# Power_Supply.net
KiCad netlist of a schematic drawn in Altium Designer
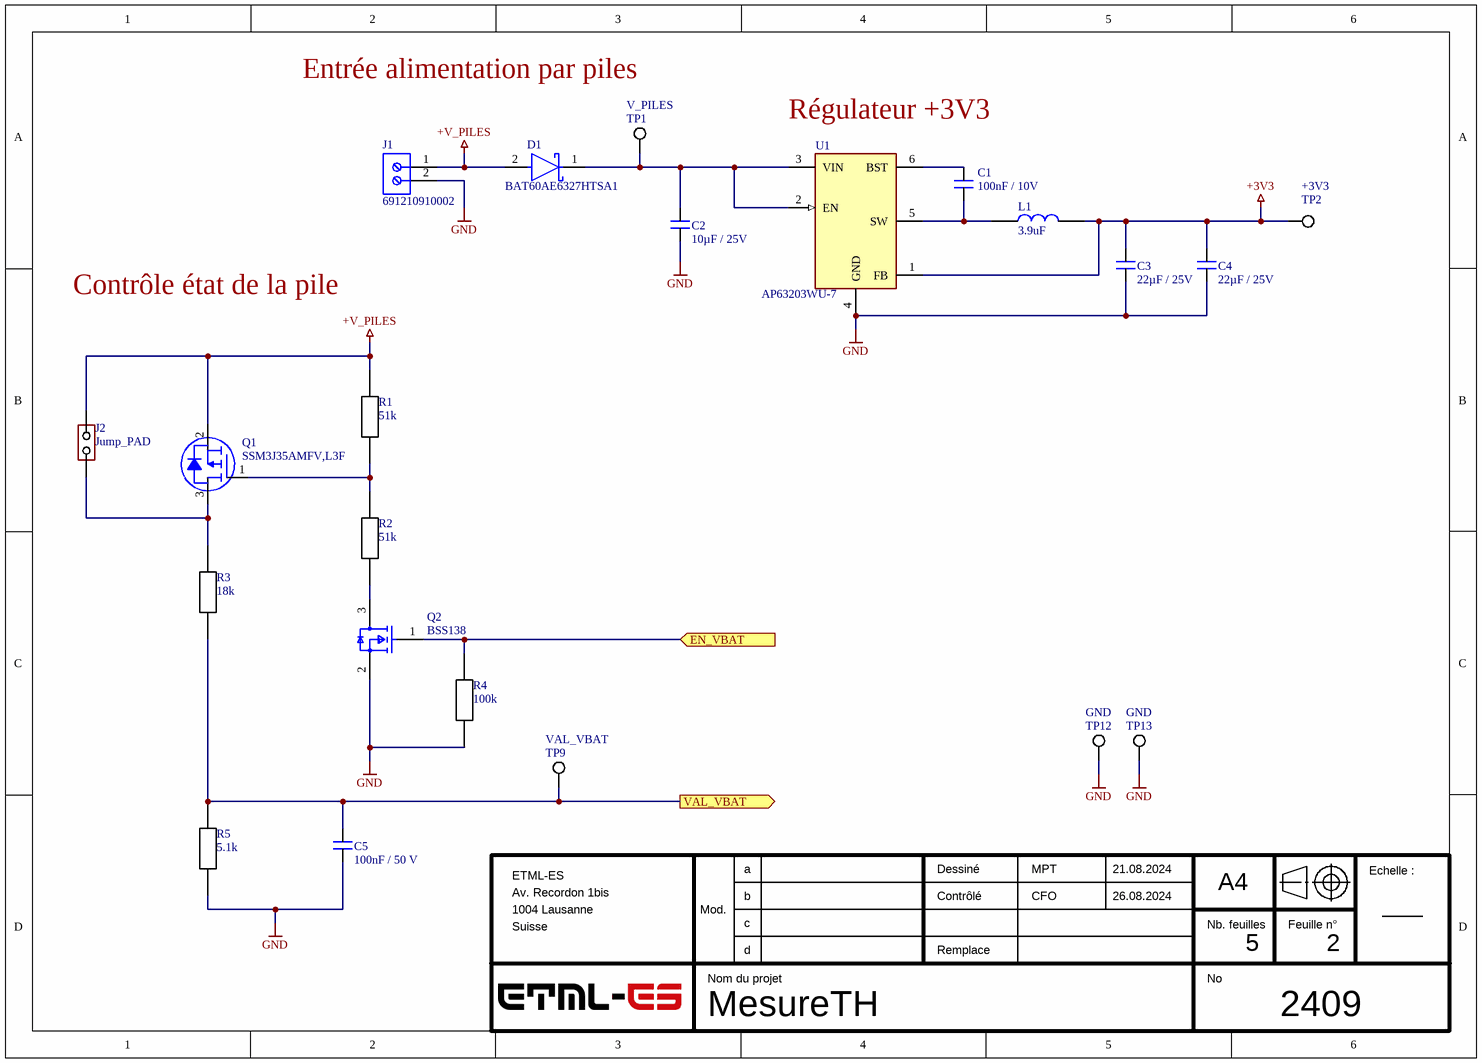
[diagram p0: Power_Supply.SchDoc]

(export (version "E")
  (design (tool "Eeschema 10.0.6"))
  (components
    (comp (ref "C1")
      (value "100nF / 10V")
      (footprint "WCAP-CSGP_0805_L2W1.25H0.8_Wave")
      (libsource (lib "Composants_Projet_2409") (part "CAPA"))
    )
    (comp (ref "C2")
      (value "10µF / 25V")
      (footprint "WCAP-CSGP_0805_L2W1.25H0.8_Wave")
      (libsource (lib "Composants_Projet_2409") (part "CAPA"))
    )
    (comp (ref "C3")
      (value "22µF / 25V")
      (footprint "WCAP-CSGP_0805_L2W1.25H0.8_Wave")
      (libsource (lib "Composants_Projet_2409") (part "CAPA"))
    )
    (comp (ref "C4")
      (value "22µF / 25V")
      (footprint "WCAP-CSGP_0805_L2W1.25H0.8_Wave")
      (libsource (lib "Composants_Projet_2409") (part "CAPA"))
    )
    (comp (ref "C5")
      (value "100nF / 50 V")
      (footprint "WCAP-CSGP_0805_L2W1.25H0.8_Wave")
      (libsource (lib "Composants_Projet_2409") (part "CAPA"))
    )
    (comp (ref "D1")
      (value "BAT60AE6327HTSA1")
      (footprint "FP-PG-SOD323-2-IPC_C")
      (description "DIODE SCHOTTKY 10V 3A SOD323-2")
      (libsource (lib "Altium Content Vault") (part "1d6ec82d83fb6aee721767c19dac4b9"))
    )
    (comp (ref "J1")
      (value "691210910002")
      (footprint "691210910002")
      (libsource (lib "Altium Content Vault") (part "TBL - 1R - 02P - Screw"))
    )
    (comp (ref "J2")
      (value "Jump_PAD")
      (footprint "Jump_PAD")
      (description "jump pad smd")
      (libsource (lib "Composants_Projet_2409") (part "Jump_PAD"))
    )
    (comp (ref "L1")
      (value "3.9uF")
      (footprint "Inductance 3.9uF")
      (description "FIXED IND 3.9UH 850MA 200 MOHM")
      (fields (field (name "MF") "EPCOS") (field (name "MP") "B82432T1392K000"))
      (libsource (lib "Composants_Projet_2409") (part "Inductance 3.9uF"))
    )
    (comp (ref "Q1")
      (value "SSM3J35AMFV,L3F")
      (footprint "SSM3J35AMFV")
      (description "Canal P 20 V 250mA (Ta) 150mW (Ta) Montage en surface VESM")
      (libsource (lib "Composants_Projet_2409") (part "SSM3J35AMFV,L3F"))
    )
    (comp (ref "Q2")
      (value "BSS138")
      (footprint "FP-318-08-IPC_B")
      (description "MOSFET N-CH 50V 220MA SOT-23")
      (libsource (lib "Altium Content Vault") (part "3b9c635fedb024a5347a57b145af9cc"))
    )
    (comp (ref "R1")
      (value "51k")
      (footprint "WRIS-PSMB_0805_L2W1.25H0.35")
      (libsource (lib "Composants_Projet_2409") (part "Resistance"))
    )
    (comp (ref "R2")
      (value "51k")
      (footprint "WRIS-PSMB_0805_L2W1.25H0.35")
      (libsource (lib "Composants_Projet_2409") (part "Resistance"))
    )
    (comp (ref "R3")
      (value "18k")
      (footprint "WRIS-PSMB_0805_L2W1.25H0.35")
      (libsource (lib "Composants_Projet_2409") (part "Resistance"))
    )
    (comp (ref "R4")
      (value "100k")
      (footprint "WRIS-PSMB_0805_L2W1.25H0.35")
      (libsource (lib "Composants_Projet_2409") (part "Resistance"))
    )
    (comp (ref "R5")
      (value "5.1k")
      (footprint "WRIS-PSMB_0805_L2W1.25H0.35")
      (libsource (lib "Composants_Projet_2409") (part "Resistance"))
    )
    (comp (ref "TP1")
      (value "Test_Point_SMD")
      (footprint "5019")
      (libsource (lib "Composants_Projet_2409") (part "Test_Point_SMD"))
    )
    (comp (ref "TP2")
      (value "Test_Point_SMD")
      (footprint "5019")
      (libsource (lib "Composants_Projet_2409") (part "Test_Point_SMD"))
    )
    (comp (ref "TP9")
      (value "Test_Point_SMD")
      (footprint "5019")
      (libsource (lib "Composants_Projet_2409") (part "Test_Point_SMD"))
    )
    (comp (ref "TP12")
      (value "Test_Point_SMD")
      (footprint "5019")
      (libsource (lib "Composants_Projet_2409") (part "Test_Point_SMD"))
    )
    (comp (ref "TP13")
      (value "Test_Point_SMD")
      (footprint "5019")
      (libsource (lib "Composants_Projet_2409") (part "Test_Point_SMD"))
    )
    (comp (ref "U1")
      (value "AP63203WU-7")
      (footprint "FP-TSOT26-MFG - duplicate")
      (description "IC REG BUCK 3.3V 2A TSOT26")
      (fields
        (field (name "MANUFACTURER") "Diodes Inc.")
        (field (name "OCTOPART") "https://octopart.com/ap63203wu-7-diodes+inc.-98099550")
      )
      (libsource (lib "Composants_Projet_2409") (part "Regulateur 3.3V"))
    )
  )
  (nets
    (net (code "1") (name "+3V3") (class "Default")
      (node (ref "C3") (pin "1") (pinfunction "+_1") (pintype "passive"))
      (node (ref "C4") (pin "1") (pinfunction "+_1") (pintype "passive"))
      (node (ref "L1") (pin "2") (pinfunction "2_2") (pintype "passive"))
      (node (ref "TP2") (pin "1") (pinfunction "1_1") (pintype "passive"))
      (node (ref "U1") (pin "1") (pinfunction "FB_1") (pintype "passive"))
    )
    (net (code "2") (name "+V_PILES") (class "Default")
      (node (ref "D1") (pin "2") (pinfunction "A_2") (pintype "passive"))
      (node (ref "J1") (pin "1") (pinfunction "1_1") (pintype "passive"))
      (node (ref "J2") (pin "2") (pintype "passive"))
      (node (ref "Q1") (pin "2") (pinfunction "S_2") (pintype "passive"))
      (node (ref "R1") (pin "2") (pinfunction "2_2") (pintype "passive"))
    )
    (net (code "3") (name "/EN_VBAT") (class "Default")
      (node (ref "Q2") (pin "1") (pinfunction "G_1") (pintype "passive"))
      (node (ref "R4") (pin "2") (pinfunction "2_2") (pintype "passive"))
    )
    (net (code "4") (name "/VAL_VBAT") (class "Default")
      (node (ref "C5") (pin "1") (pinfunction "+_1") (pintype "passive"))
      (node (ref "R3") (pin "1") (pinfunction "1_1") (pintype "passive"))
      (node (ref "R5") (pin "2") (pinfunction "2_2") (pintype "passive"))
      (node (ref "TP9") (pin "1") (pinfunction "1_1") (pintype "passive"))
    )
    (net (code "5") (name "GND") (class "Default")
      (node (ref "C2") (pin "2") (pinfunction "-_2") (pintype "passive"))
      (node (ref "C3") (pin "2") (pinfunction "-_2") (pintype "passive"))
      (node (ref "C4") (pin "2") (pinfunction "-_2") (pintype "passive"))
      (node (ref "C5") (pin "2") (pinfunction "-_2") (pintype "passive"))
      (node (ref "J1") (pin "2") (pinfunction "2_2") (pintype "passive"))
      (node (ref "Q2") (pin "2") (pinfunction "S_2") (pintype "passive"))
      (node (ref "R4") (pin "1") (pinfunction "1_1") (pintype "passive"))
      (node (ref "R5") (pin "1") (pinfunction "1_1") (pintype "passive"))
      (node (ref "TP12") (pin "1") (pinfunction "1_1") (pintype "passive"))
      (node (ref "TP13") (pin "1") (pinfunction "1_1") (pintype "passive"))
      (node (ref "U1") (pin "4") (pinfunction "GND_4") (pintype "power_in"))
    )
    (net (code "6") (name "Net-(C1-+)") (class "Default")
      (node (ref "C1") (pin "1") (pinfunction "+_1") (pintype "passive"))
      (node (ref "U1") (pin "6") (pinfunction "BST_6") (pintype "passive"))
    )
    (net (code "7") (name "Net-(C1--)") (class "Default")
      (node (ref "C1") (pin "2") (pinfunction "-_2") (pintype "passive"))
      (node (ref "L1") (pin "1") (pinfunction "1_1") (pintype "passive"))
      (node (ref "U1") (pin "5") (pinfunction "SW_5") (pintype "power_in"))
    )
    (net (code "8") (name "Net-(C2-+)") (class "Default")
      (node (ref "C2") (pin "1") (pinfunction "+_1") (pintype "passive"))
      (node (ref "D1") (pin "1") (pinfunction "C_1") (pintype "passive"))
      (node (ref "TP1") (pin "1") (pinfunction "1_1") (pintype "passive"))
      (node (ref "U1") (pin "2") (pinfunction "EN_2") (pintype "input"))
      (node (ref "U1") (pin "3") (pinfunction "VIN_3") (pintype "power_in"))
    )
    (net (code "9") (name "Net-(Q1-D)") (class "Default")
      (node (ref "J2") (pin "1") (pintype "passive"))
      (node (ref "Q1") (pin "3") (pinfunction "D_3") (pintype "passive"))
      (node (ref "R3") (pin "2") (pinfunction "2_2") (pintype "passive"))
    )
    (net (code "10") (name "Net-(Q1-G)") (class "Default")
      (node (ref "Q1") (pin "1") (pinfunction "G_1") (pintype "passive"))
      (node (ref "R1") (pin "1") (pinfunction "1_1") (pintype "passive"))
      (node (ref "R2") (pin "2") (pinfunction "2_2") (pintype "passive"))
    )
    (net (code "11") (name "Net-(Q2-D)") (class "Default")
      (node (ref "Q2") (pin "3") (pinfunction "D_3") (pintype "passive"))
      (node (ref "R2") (pin "1") (pinfunction "1_1") (pintype "passive"))
    )
  )
)
